# System.net
KiCad netlist of a schematic drawn in Altium Designer
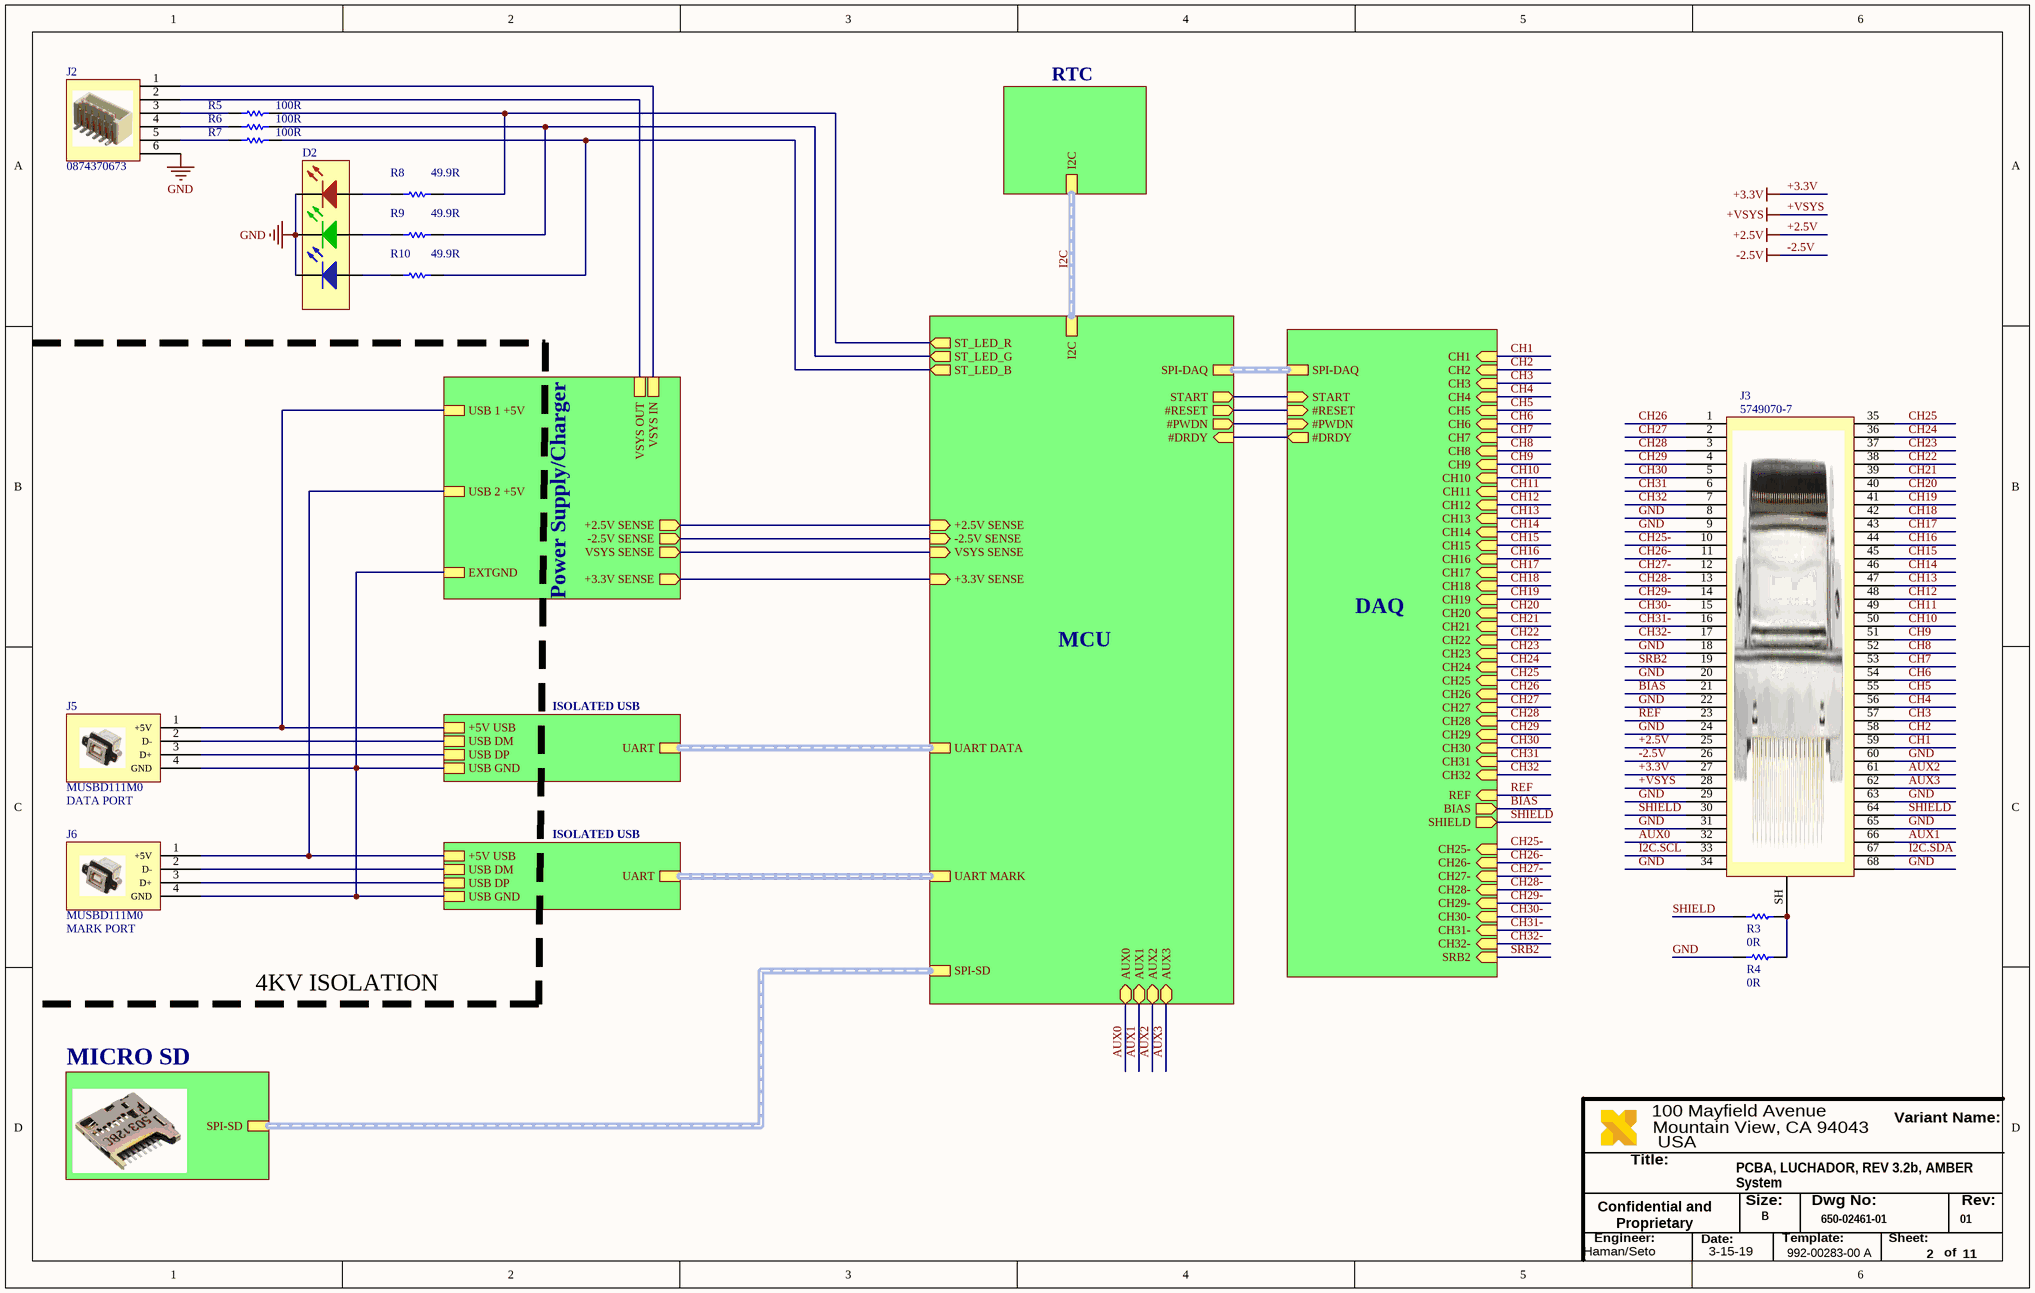
[diagram p0: System.SchDoc]

(export (version "E")
  (design (tool "Eeschema 10.0.6"))
  (components
    (comp (ref "D2")
      (value "Component_2")
      (footprint "ASMB-TTB0-0A3A2")
      (fields
        (field (name "MANUFACTURER") "Broadcom Avago")
        (field (name "MANUFACTURER PART NUMBER") "ASMB-TTB0-0A3A2")
      )
      (libsource (lib "LUCHADOR SCHLIB") (part "Component_2"))
    )
    (comp (ref "J2")
      (value "POWER SWITCH")
      (footprint "0874370673")
      (fields (field (name "MANUFACTURER") "Molex") (field (name "MANUFACTURER PART NUMBER") "0874370673"))
      (libsource (lib "LUCHADOR SCHLIB") (part "0874370673"))
    )
    (comp (ref "J3")
      (value "10268-6212PC")
      (footprint "5749070-7")
      (fields
        (field (name "MANUFACTURER") "AMP - TE CONNECTIVITY")
        (field (name "MANUFACTURER PART NUMBER") "5749070-7")
      )
      (libsource (lib "LUCHADOR SCHLIB") (part "10268-6212PC"))
    )
    (comp (ref "J5")
      (value "DATA PORT")
      (footprint "MUSBD111M0")
      (fields
        (field (name "MANUFACTURER") "Amphenol Commercial Products")
        (field (name "MANUFACTURER PART NUMBER") "MUSBD111M0")
      )
      (libsource (lib "PI2PCUBS SCHLIB") (part "MUSBD111M0"))
    )
    (comp (ref "J6")
      (value "MARK PORT")
      (footprint "MUSBD111M0")
      (fields
        (field (name "MANUFACTURER") "Amphenol Commercial Products")
        (field (name "MANUFACTURER PART NUMBER") "MUSBD111M0")
      )
      (libsource (lib "PI2PCUBS SCHLIB") (part "MUSBD111M0"))
    )
    (comp (ref "R3")
      (value "Res 0805")
      (footprint "0402R")
      (description "Resistor")
      (fields
        (field (name "MANUFACTURER") "Panasonic")
        (field (name "MANUFACTURER PART NUMBER") "ERJ-2GE0R00X")
        (field (name "RESISTANCE (OHMS)") "0R")
      )
      (libsource (lib "RAPTOR MCB SCHLIB") (part "Res 0805"))
    )
    (comp (ref "R4")
      (value "Res 0805")
      (footprint "0402R")
      (description "Resistor")
      (fields
        (field (name "MANUFACTURER") "Panasonic")
        (field (name "MANUFACTURER PART NUMBER") "ERJ-2GE0R00X")
        (field (name "RESISTANCE (OHMS)") "0R")
      )
      (libsource (lib "RAPTOR MCB SCHLIB") (part "Res 0805"))
    )
    (comp (ref "R5")
      (value "Res 0805")
      (footprint "0402R")
      (description "Resistor")
      (fields
        (field (name "MANUFACTURER") "Panasonic")
        (field (name "MANUFACTURER PART NUMBER") "ERJ-2RKF1000X")
        (field (name "RESISTANCE") "100R")
      )
      (libsource (lib "RAPTOR MCB SCHLIB") (part "Res 0805"))
    )
    (comp (ref "R6")
      (value "Res 0805")
      (footprint "0402R")
      (description "Resistor")
      (fields
        (field (name "MANUFACTURER") "Panasonic")
        (field (name "MANUFACTURER PART NUMBER") "ERJ-2RKF1000X")
        (field (name "RESISTANCE") "100R")
      )
      (libsource (lib "RAPTOR MCB SCHLIB") (part "Res 0805"))
    )
    (comp (ref "R7")
      (value "Res 0805")
      (footprint "0402R")
      (description "Resistor")
      (fields
        (field (name "MANUFACTURER") "Panasonic")
        (field (name "MANUFACTURER PART NUMBER") "ERJ-2RKF1000X")
        (field (name "RESISTANCE") "100R")
      )
      (libsource (lib "RAPTOR MCB SCHLIB") (part "Res 0805"))
    )
    (comp (ref "R8")
      (value "Res 0805")
      (footprint "0402R")
      (description "Resistor")
      (fields
        (field (name "MANUFACTURER") "Yageo")
        (field (name "MANUFACTURER PART NUMBER") "RC0402FR-0749R9L")
        (field (name "RESISTANCE (OHMS)") "49.9R")
      )
      (libsource (lib "RAPTOR MCB SCHLIB") (part "Res 0805"))
    )
    (comp (ref "R9")
      (value "Res 0805")
      (footprint "0402R")
      (description "Resistor")
      (fields
        (field (name "MANUFACTURER") "Yageo")
        (field (name "MANUFACTURER PART NUMBER") "RC0402FR-0749R9L")
        (field (name "RESISTANCE (OHMS)") "49.9R")
      )
      (libsource (lib "RAPTOR MCB SCHLIB") (part "Res 0805"))
    )
    (comp (ref "R10")
      (value "Res 0805")
      (footprint "0402R")
      (description "Resistor")
      (fields
        (field (name "MANUFACTURER") "Yageo")
        (field (name "MANUFACTURER PART NUMBER") "RC0402FR-0749R9L")
        (field (name "RESISTANCE (OHMS)") "49.9R")
      )
      (libsource (lib "RAPTOR MCB SCHLIB") (part "Res 0805"))
    )
  )
  (nets
    (net (code "2") (name "+2.5V") (class "Default")
      (node (ref "J3") (pin "25") (pinfunction "25_25") (pintype "passive"))
    )
    (net (code "3") (name "+3.3V") (class "Default")
      (node (ref "J3") (pin "27") (pinfunction "27_27") (pintype "passive"))
    )
    (net (code "4") (name "+VSYS") (class "Default")
      (node (ref "J3") (pin "28") (pinfunction "28_28") (pintype "passive"))
    )
    (net (code "5") (name "-2.5V") (class "Default")
      (node (ref "J3") (pin "26") (pinfunction "26_26") (pintype "passive"))
    )
    (net (code "11") (name "/+5V USB") (class "Default")
      (node (ref "J5") (pin "1") (pinfunction "+5V_1") (pintype "passive"))
    )
    (net (code "12") (name "/+5V USB_1") (class "Default")
      (node (ref "J6") (pin "1") (pinfunction "+5V_1") (pintype "passive"))
    )
    (net (code "14") (name "/AUX0") (class "Default")
      (node (ref "J3") (pin "32") (pinfunction "32_32") (pintype "passive"))
    )
    (net (code "15") (name "/AUX1") (class "Default")
      (node (ref "J3") (pin "66") (pinfunction "66_66") (pintype "passive"))
    )
    (net (code "16") (name "/AUX2") (class "Default")
      (node (ref "J3") (pin "61") (pinfunction "61_61") (pintype "passive"))
    )
    (net (code "17") (name "/AUX3") (class "Default")
      (node (ref "J3") (pin "62") (pinfunction "62_62") (pintype "passive"))
    )
    (net (code "18") (name "/BIAS") (class "Default")
      (node (ref "J3") (pin "21") (pinfunction "21_21") (pintype "passive"))
    )
    (net (code "19") (name "/CH1") (class "Default")
      (node (ref "J3") (pin "59") (pinfunction "59_59") (pintype "passive"))
    )
    (net (code "20") (name "/CH2") (class "Default")
      (node (ref "J3") (pin "58") (pinfunction "58_58") (pintype "passive"))
    )
    (net (code "21") (name "/CH3") (class "Default")
      (node (ref "J3") (pin "57") (pinfunction "57_57") (pintype "passive"))
    )
    (net (code "22") (name "/CH4") (class "Default")
      (node (ref "J3") (pin "56") (pinfunction "56_56") (pintype "passive"))
    )
    (net (code "23") (name "/CH5") (class "Default")
      (node (ref "J3") (pin "55") (pinfunction "55_55") (pintype "passive"))
    )
    (net (code "24") (name "/CH6") (class "Default")
      (node (ref "J3") (pin "54") (pinfunction "54_54") (pintype "passive"))
    )
    (net (code "25") (name "/CH7") (class "Default")
      (node (ref "J3") (pin "53") (pinfunction "53_53") (pintype "passive"))
    )
    (net (code "26") (name "/CH8") (class "Default")
      (node (ref "J3") (pin "52") (pinfunction "52_52") (pintype "passive"))
    )
    (net (code "27") (name "/CH9") (class "Default")
      (node (ref "J3") (pin "51") (pinfunction "51_51") (pintype "passive"))
    )
    (net (code "28") (name "/CH10") (class "Default")
      (node (ref "J3") (pin "50") (pinfunction "50_50") (pintype "passive"))
    )
    (net (code "29") (name "/CH11") (class "Default")
      (node (ref "J3") (pin "49") (pinfunction "49_49") (pintype "passive"))
    )
    (net (code "30") (name "/CH12") (class "Default")
      (node (ref "J3") (pin "48") (pinfunction "48_48") (pintype "passive"))
    )
    (net (code "31") (name "/CH13") (class "Default")
      (node (ref "J3") (pin "47") (pinfunction "47_47") (pintype "passive"))
    )
    (net (code "32") (name "/CH14") (class "Default")
      (node (ref "J3") (pin "46") (pinfunction "46_46") (pintype "passive"))
    )
    (net (code "33") (name "/CH15") (class "Default")
      (node (ref "J3") (pin "45") (pinfunction "45_45") (pintype "passive"))
    )
    (net (code "34") (name "/CH16") (class "Default")
      (node (ref "J3") (pin "44") (pinfunction "44_44") (pintype "passive"))
    )
    (net (code "35") (name "/CH17") (class "Default")
      (node (ref "J3") (pin "43") (pinfunction "43_43") (pintype "passive"))
    )
    (net (code "36") (name "/CH18") (class "Default")
      (node (ref "J3") (pin "42") (pinfunction "42_42") (pintype "passive"))
    )
    (net (code "37") (name "/CH19") (class "Default")
      (node (ref "J3") (pin "41") (pinfunction "41_41") (pintype "passive"))
    )
    (net (code "38") (name "/CH20") (class "Default")
      (node (ref "J3") (pin "40") (pinfunction "40_40") (pintype "passive"))
    )
    (net (code "39") (name "/CH21") (class "Default")
      (node (ref "J3") (pin "39") (pinfunction "39_39") (pintype "passive"))
    )
    (net (code "40") (name "/CH22") (class "Default")
      (node (ref "J3") (pin "38") (pinfunction "38_38") (pintype "passive"))
    )
    (net (code "41") (name "/CH23") (class "Default")
      (node (ref "J3") (pin "37") (pinfunction "37_37") (pintype "passive"))
    )
    (net (code "42") (name "/CH24") (class "Default")
      (node (ref "J3") (pin "36") (pinfunction "36_36") (pintype "passive"))
    )
    (net (code "43") (name "/CH25") (class "Default")
      (node (ref "J3") (pin "35") (pinfunction "35_35") (pintype "passive"))
    )
    (net (code "44") (name "/CH25-") (class "Default")
      (node (ref "J3") (pin "10") (pinfunction "10_10") (pintype "passive"))
    )
    (net (code "45") (name "/CH26") (class "Default")
      (node (ref "J3") (pin "1") (pinfunction "1_1") (pintype "passive"))
    )
    (net (code "46") (name "/CH26-") (class "Default")
      (node (ref "J3") (pin "11") (pinfunction "11_11") (pintype "passive"))
    )
    (net (code "47") (name "/CH27") (class "Default")
      (node (ref "J3") (pin "2") (pinfunction "2_2") (pintype "passive"))
    )
    (net (code "48") (name "/CH27-") (class "Default")
      (node (ref "J3") (pin "12") (pinfunction "12_12") (pintype "passive"))
    )
    (net (code "49") (name "/CH28") (class "Default")
      (node (ref "J3") (pin "3") (pinfunction "3_3") (pintype "passive"))
    )
    (net (code "50") (name "/CH28-") (class "Default")
      (node (ref "J3") (pin "13") (pinfunction "13_13") (pintype "passive"))
    )
    (net (code "51") (name "/CH29") (class "Default")
      (node (ref "J3") (pin "4") (pinfunction "4_4") (pintype "passive"))
    )
    (net (code "52") (name "/CH29-") (class "Default")
      (node (ref "J3") (pin "14") (pinfunction "14_14") (pintype "passive"))
    )
    (net (code "53") (name "/CH30") (class "Default")
      (node (ref "J3") (pin "5") (pinfunction "5_5") (pintype "passive"))
    )
    (net (code "54") (name "/CH30-") (class "Default")
      (node (ref "J3") (pin "15") (pinfunction "15_15") (pintype "passive"))
    )
    (net (code "55") (name "/CH31") (class "Default")
      (node (ref "J3") (pin "6") (pinfunction "6_6") (pintype "passive"))
    )
    (net (code "56") (name "/CH31-") (class "Default")
      (node (ref "J3") (pin "16") (pinfunction "16_16") (pintype "passive"))
    )
    (net (code "57") (name "/CH32") (class "Default")
      (node (ref "J3") (pin "7") (pinfunction "7_7") (pintype "passive"))
    )
    (net (code "58") (name "/CH32-") (class "Default")
      (node (ref "J3") (pin "17") (pinfunction "17_17") (pintype "passive"))
    )
    (net (code "59") (name "/EXTGND") (class "Default")
      (node (ref "J5") (pin "4") (pinfunction "GND_4") (pintype "passive"))
      (node (ref "J6") (pin "4") (pinfunction "GND_4") (pintype "passive"))
    )
    (net (code "60") (name "/I2C.SCL") (class "Default")
      (node (ref "J3") (pin "33") (pinfunction "33_33") (pintype "passive"))
    )
    (net (code "61") (name "/I2C.SDA") (class "Default")
      (node (ref "J3") (pin "67") (pinfunction "67_67") (pintype "passive"))
    )
    (net (code "62") (name "/REF") (class "Default")
      (node (ref "J3") (pin "23") (pinfunction "23_23") (pintype "passive"))
    )
    (net (code "63") (name "/SHIELD") (class "Default")
      (node (ref "J3") (pin "30") (pinfunction "30_30") (pintype "passive"))
      (node (ref "J3") (pin "64") (pinfunction "64_64") (pintype "passive"))
      (node (ref "R3") (pin "1") (pinfunction "1_1") (pintype "passive"))
    )
    (net (code "66") (name "/SRB2") (class "Default")
      (node (ref "J3") (pin "19") (pinfunction "19_19") (pintype "passive"))
    )
    (net (code "68") (name "/ST_LED_B") (class "Default")
      (node (ref "R10") (pin "2") (pinfunction "2_2") (pintype "passive"))
      (node (ref "R7") (pin "2") (pinfunction "2_2") (pintype "passive"))
    )
    (net (code "69") (name "/ST_LED_G") (class "Default")
      (node (ref "R6") (pin "2") (pinfunction "2_2") (pintype "passive"))
      (node (ref "R9") (pin "2") (pinfunction "2_2") (pintype "passive"))
    )
    (net (code "70") (name "/ST_LED_R") (class "Default")
      (node (ref "R5") (pin "2") (pinfunction "2_2") (pintype "passive"))
      (node (ref "R8") (pin "2") (pinfunction "2_2") (pintype "passive"))
    )
    (net (code "73") (name "/USB DM") (class "Default")
      (node (ref "J6") (pin "2") (pinfunction "D-_2") (pintype "passive"))
    )
    (net (code "74") (name "/USB DM_1") (class "Default")
      (node (ref "J5") (pin "2") (pinfunction "D-_2") (pintype "passive"))
    )
    (net (code "75") (name "/USB DP") (class "Default")
      (node (ref "J6") (pin "3") (pinfunction "D+_3") (pintype "passive"))
    )
    (net (code "76") (name "/USB DP_1") (class "Default")
      (node (ref "J5") (pin "3") (pinfunction "D+_3") (pintype "passive"))
    )
    (net (code "77") (name "/VSYS IN") (class "Default")
      (node (ref "J2") (pin "1") (pinfunction "1_1") (pintype "passive"))
    )
    (net (code "78") (name "/VSYS OUT") (class "Default")
      (node (ref "J2") (pin "2") (pinfunction "2_2") (pintype "passive"))
    )
    (net (code "81") (name "GND") (class "Default")
      (node (ref "D2") (pin "1") (pinfunction "K_1") (pintype "passive"))
      (node (ref "D2") (pin "2") (pinfunction "K_2") (pintype "passive"))
      (node (ref "D2") (pin "3") (pinfunction "K_3") (pintype "passive"))
      (node (ref "J2") (pin "6") (pinfunction "6_6") (pintype "passive"))
      (node (ref "J3") (pin "18") (pinfunction "18_18") (pintype "passive"))
      (node (ref "J3") (pin "20") (pinfunction "20_20") (pintype "passive"))
      (node (ref "J3") (pin "22") (pinfunction "22_22") (pintype "passive"))
      (node (ref "J3") (pin "24") (pinfunction "24_24") (pintype "passive"))
      (node (ref "J3") (pin "29") (pinfunction "29_29") (pintype "passive"))
      (node (ref "J3") (pin "31") (pinfunction "31_31") (pintype "passive"))
      (node (ref "J3") (pin "34") (pinfunction "34_34") (pintype "passive"))
      (node (ref "J3") (pin "60") (pinfunction "60_60") (pintype "passive"))
      (node (ref "J3") (pin "63") (pinfunction "63_63") (pintype "passive"))
      (node (ref "J3") (pin "65") (pinfunction "65_65") (pintype "passive"))
      (node (ref "J3") (pin "68") (pinfunction "68_68") (pintype "passive"))
      (node (ref "J3") (pin "8") (pinfunction "8_8") (pintype "passive"))
      (node (ref "J3") (pin "9") (pinfunction "9_9") (pintype "passive"))
      (node (ref "R4") (pin "1") (pinfunction "1_1") (pintype "passive"))
    )
    (net (code "82") (name "Net-(D2-A-Pad4)") (class "Default")
      (node (ref "D2") (pin "4") (pinfunction "A_4") (pintype "passive"))
      (node (ref "R8") (pin "1") (pinfunction "1_1") (pintype "passive"))
    )
    (net (code "83") (name "Net-(D2-A-Pad5)") (class "Default")
      (node (ref "D2") (pin "5") (pinfunction "A_5") (pintype "passive"))
      (node (ref "R9") (pin "1") (pinfunction "1_1") (pintype "passive"))
    )
    (net (code "84") (name "Net-(D2-A-Pad6)") (class "Default")
      (node (ref "D2") (pin "6") (pinfunction "A_6") (pintype "passive"))
      (node (ref "R10") (pin "1") (pinfunction "1_1") (pintype "passive"))
    )
    (net (code "85") (name "Net-(J2-Pad3)") (class "Default")
      (node (ref "J2") (pin "3") (pinfunction "3_3") (pintype "passive"))
      (node (ref "R5") (pin "1") (pinfunction "1_1") (pintype "passive"))
    )
    (net (code "86") (name "Net-(J2-Pad4)") (class "Default")
      (node (ref "J2") (pin "4") (pinfunction "4_4") (pintype "passive"))
      (node (ref "R6") (pin "1") (pinfunction "1_1") (pintype "passive"))
    )
    (net (code "87") (name "Net-(J2-Pad5)") (class "Default")
      (node (ref "J2") (pin "5") (pinfunction "5_5") (pintype "passive"))
      (node (ref "R7") (pin "1") (pinfunction "1_1") (pintype "passive"))
    )
    (net (code "88") (name "Net-(J3-PadSH)") (class "Default")
      (node (ref "J3") (pin "SH") (pinfunction "SH_SH") (pintype "passive"))
      (node (ref "R3") (pin "2") (pinfunction "2_2") (pintype "passive"))
      (node (ref "R4") (pin "2") (pinfunction "2_2") (pintype "passive"))
    )
  )
)
